# tvout_terminal_v1_1.net
KiCad netlist of a schematic drawn in EAGLE
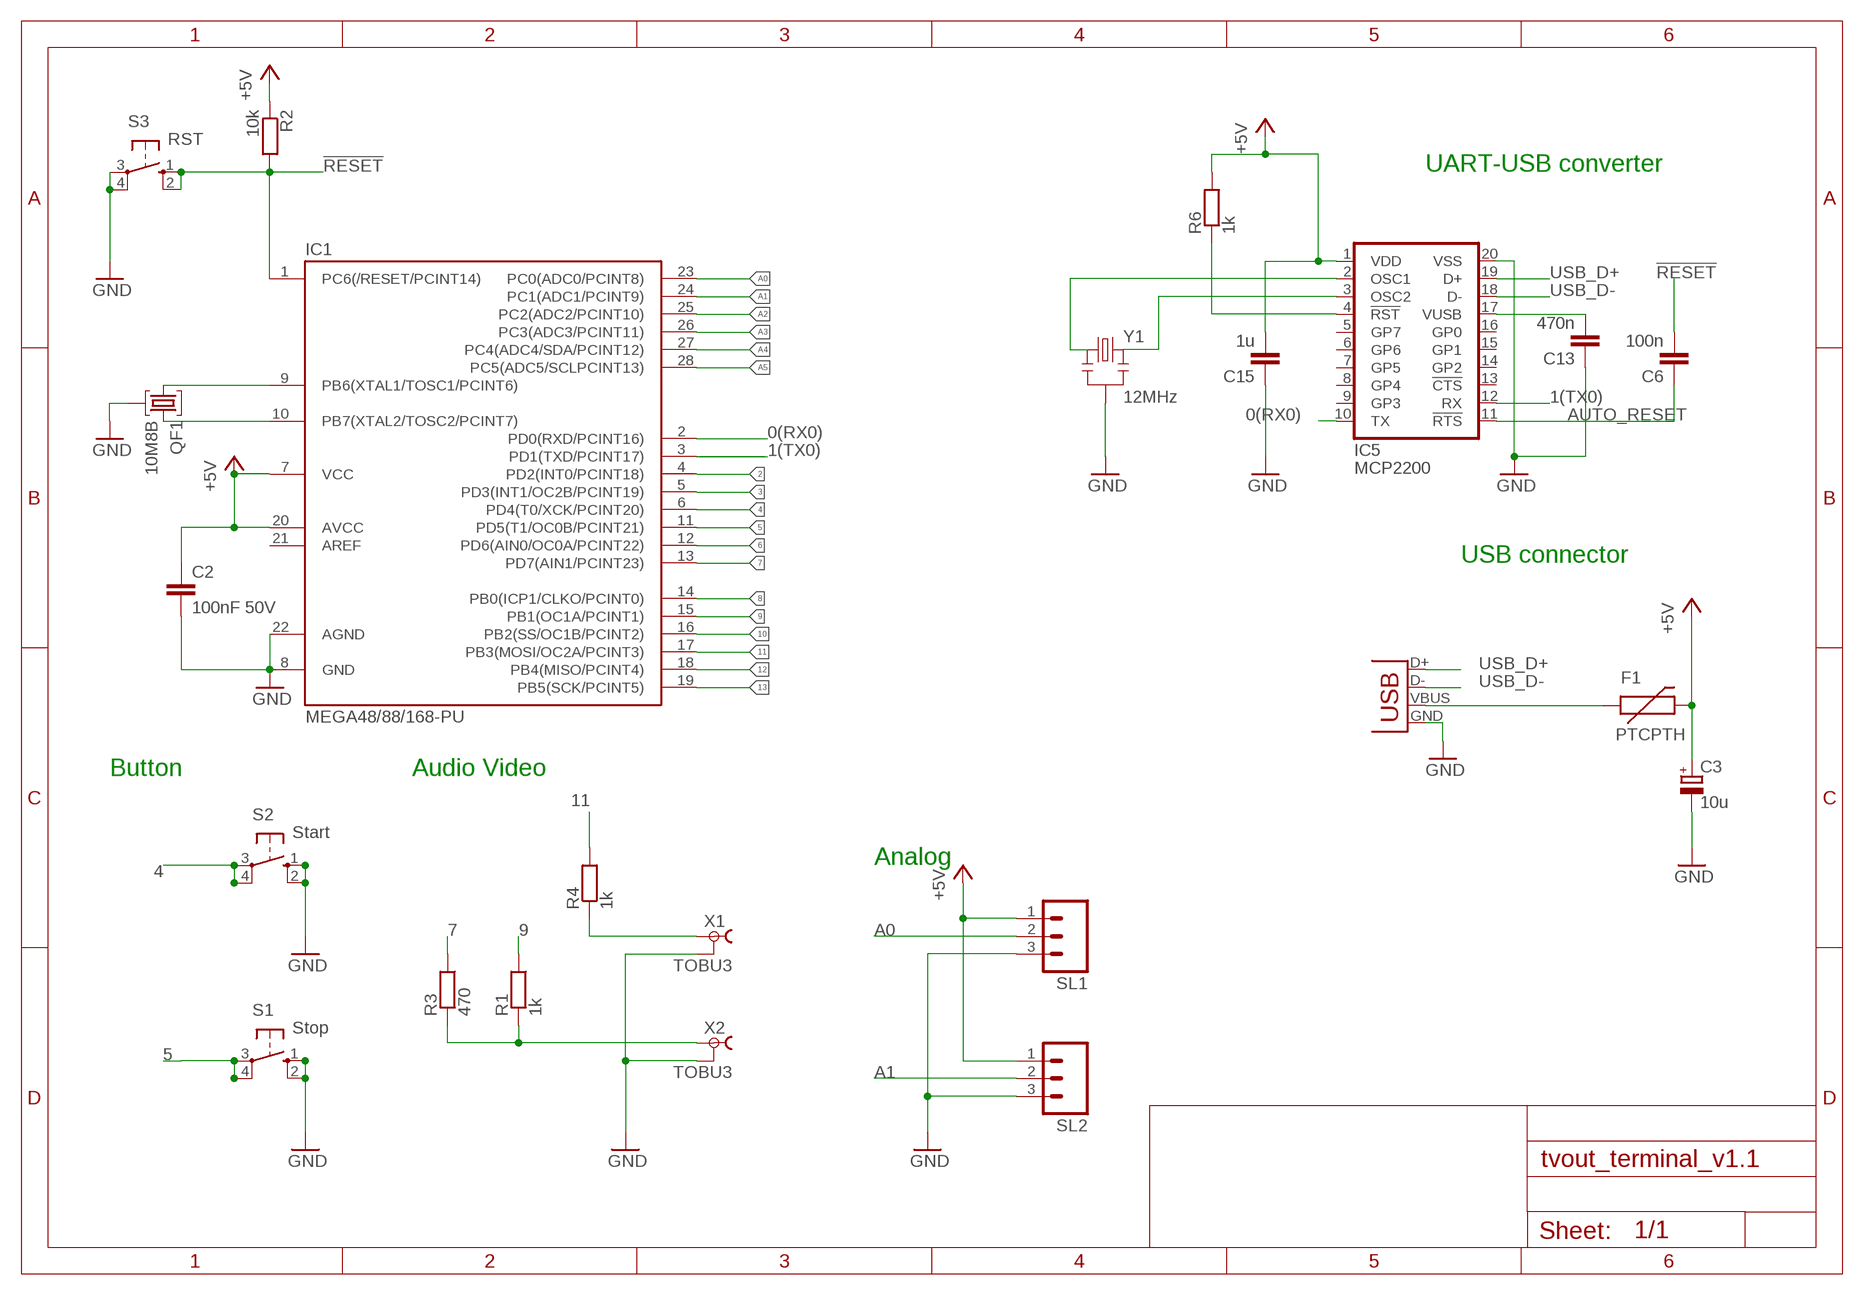
[diagram p0: schematic, sheet 1]

(export (version "E")
  (design (tool "Eeschema 10.0.6"))
  (components
    (comp (ref "C2")
      (value "100nF 50V")
      (footprint "eagle-import:C025-025X050")
      (libsource (lib "eagle-import") (part "C-EU025-025X050"))
    )
    (comp (ref "C3")
      (value "10u")
      (footprint "eagle-import:E2,5-7")
      (libsource (lib "eagle-import") (part "CPOL-EUE2.5-7"))
    )
    (comp (ref "C6")
      (value "100n")
      (footprint "eagle-import:CAP-PTH-SMALL")
      (libsource (lib "eagle-import") (part "CAPPTH"))
    )
    (comp (ref "C13")
      (value "470n")
      (footprint "eagle-import:CAP-PTH-SMALL")
      (libsource (lib "eagle-import") (part "CAPPTH"))
    )
    (comp (ref "C15")
      (value "1u")
      (footprint "eagle-import:CAP-PTH-5MM")
      (libsource (lib "eagle-import") (part "CAPPTH1"))
    )
    (comp (ref "F1")
      (value "PTCPTH")
      (footprint "eagle-import:PTC")
      (libsource (lib "eagle-import") (part "PTCPTH"))
    )
    (comp (ref "IC1")
      (value "MEGA48/88/168-PU")
      (footprint "eagle-import:DIL28-3")
      (libsource (lib "eagle-import") (part "MEGA48/88/168-PU"))
    )
    (comp (ref "IC5")
      (value "MCP2200")
      (footprint "eagle-import:SO20")
      (libsource (lib "eagle-import") (part "MCP2200"))
    )
    (comp (ref "QF1")
      (value "10M8B")
      (footprint "eagle-import:HC49U")
      (fields (field (name "OC_FARNELL") "1448129"))
      (libsource (lib "eagle-import") (part "10MB8"))
    )
    (comp (ref "R1")
      (value "1k")
      (footprint "eagle-import:RES-AXIAL-0.4")
      (libsource (lib "eagle-import") (part "RESISTOR"))
    )
    (comp (ref "R2")
      (value "10k")
      (footprint "eagle-import:RES-AXIAL-0.4")
      (libsource (lib "eagle-import") (part "RESISTOR"))
    )
    (comp (ref "R3")
      (value "470")
      (footprint "eagle-import:RES-AXIAL-0.4")
      (libsource (lib "eagle-import") (part "RESISTOR"))
    )
    (comp (ref "R4")
      (value "1k")
      (footprint "eagle-import:RES-AXIAL-0.4")
      (libsource (lib "eagle-import") (part "RESISTOR"))
    )
    (comp (ref "R6")
      (value "1k")
      (footprint "eagle-import:RES-AXIAL-0.4")
      (libsource (lib "eagle-import") (part "RESISTOR"))
    )
    (comp (ref "S1")
      (value "Stop")
      (footprint "eagle-import:B3F-10XX")
      (fields (field (name "MPN") "B3F-1000"))
      (libsource (lib "eagle-import") (part "10-XX"))
    )
    (comp (ref "S2")
      (value "Start")
      (footprint "eagle-import:B3F-10XX")
      (fields (field (name "MPN") "B3F-1000"))
      (libsource (lib "eagle-import") (part "10-XX"))
    )
    (comp (ref "S3")
      (value "RST")
      (footprint "eagle-import:B3F-10XX")
      (fields (field (name "MPN") "B3F-1000"))
      (libsource (lib "eagle-import") (part "10-XX"))
    )
    (comp (ref "SL1")
      (value "M03")
      (footprint "eagle-import:03P")
      (fields (field (name "OC_FARNELL") "1675765"))
      (libsource (lib "eagle-import") (part "M03"))
    )
    (comp (ref "SL2")
      (value "M03")
      (footprint "eagle-import:03P")
      (fields (field (name "OC_FARNELL") "1675765"))
      (libsource (lib "eagle-import") (part "M03"))
    )
    (comp (ref "X1")
      (value "TOBU3")
      (footprint "eagle-import:TOBU3")
      (fields (field (name "MF") "FARNELL") (field (name "MPN") "TOBU 3"))
      (libsource (lib "eagle-import") (part "TOBU3"))
    )
    (comp (ref "X2")
      (value "TOBU3")
      (footprint "eagle-import:TOBU3")
      (fields (field (name "MF") "FARNELL") (field (name "MPN") "TOBU 3"))
      (libsource (lib "eagle-import") (part "TOBU3"))
    )
    (comp (ref "X3")
      (value "USB")
      (footprint "eagle-import:USB-B-PTH")
      (libsource (lib "eagle-import") (part "USBPTH"))
    )
    (comp (ref "Y1")
      (value "12MHz")
      (footprint "eagle-import:HC49U-V-RESONATOR")
      (libsource (lib "eagle-import") (part "CRYSTAL-RESONATOR"))
    )
  )
  (nets
    (net (code "1") (name "+5V") (class "Default")
      (node (ref "C15") (pin "2") (pinfunction "2_2") (pintype "passive"))
      (node (ref "C2") (pin "1") (pinfunction "1_1") (pintype "passive"))
      (node (ref "C3") (pin "+") (pinfunction "+_+") (pintype "passive"))
      (node (ref "F1") (pin "P$2") (pinfunction "2_P$2") (pintype "bidirectional"))
      (node (ref "IC1") (pin "20") (pinfunction "AVCC_20") (pintype "passive"))
      (node (ref "IC1") (pin "7") (pinfunction "VCC_7") (pintype "power_in"))
      (node (ref "IC5") (pin "1") (pinfunction "VDD_1") (pintype "power_in"))
      (node (ref "R2") (pin "P$1") (pinfunction "1_P$1") (pintype "passive"))
      (node (ref "R6") (pin "P$2") (pinfunction "2_P$2") (pintype "passive"))
      (node (ref "SL1") (pin "1") (pinfunction "1_1") (pintype "passive"))
      (node (ref "SL2") (pin "1") (pinfunction "1_1") (pintype "passive"))
    )
    (net (code "2") (name "/0(RX0)") (class "Default")
      (node (ref "IC1") (pin "2") (pinfunction "PD0(RXD/PCINT16)_2") (pintype "bidirectional"))
      (node (ref "IC5") (pin "10") (pinfunction "TX_10") (pintype "bidirectional"))
    )
    (net (code "3") (name "/1(TX0)") (class "Default")
      (node (ref "IC1") (pin "3") (pinfunction "PD1(TXD/PCINT17)_3") (pintype "bidirectional"))
      (node (ref "IC5") (pin "12") (pinfunction "RX_12") (pintype "bidirectional"))
    )
    (net (code "4") (name "/AUTO_RESET") (class "Default")
      (node (ref "C6") (pin "1") (pinfunction "1_1") (pintype "passive"))
      (node (ref "IC5") (pin "11") (pinfunction "~{RTS}_11") (pintype "bidirectional"))
    )
    (net (code "5") (name "/USB_D+") (class "Default")
      (node (ref "IC5") (pin "19") (pinfunction "D+_19") (pintype "bidirectional"))
      (node (ref "X3") (pin "D+") (pinfunction "D+_D+") (pintype "bidirectional"))
    )
    (net (code "6") (name "/USB_D-") (class "Default")
      (node (ref "IC5") (pin "18") (pinfunction "D-_18") (pintype "bidirectional"))
      (node (ref "X3") (pin "D-") (pinfunction "D-_D-") (pintype "bidirectional"))
    )
    (net (code "7") (name "/~{RESET}") (class "Default")
      (node (ref "C6") (pin "2") (pinfunction "2_2") (pintype "passive"))
      (node (ref "IC1") (pin "1") (pinfunction "PC6(/RESET/PCINT14)_1") (pintype "bidirectional"))
      (node (ref "R2") (pin "P$2") (pinfunction "2_P$2") (pintype "passive"))
      (node (ref "S3") (pin "1") (pinfunction "S_1") (pintype "passive"))
      (node (ref "S3") (pin "2") (pinfunction "S1_2") (pintype "passive"))
    )
    (net (code "8") (name "2") (class "Default")
      (node (ref "IC1") (pin "4") (pinfunction "PD2(INT0/PCINT18)_4") (pintype "bidirectional"))
    )
    (net (code "9") (name "3") (class "Default")
      (node (ref "IC1") (pin "5") (pinfunction "PD3(INT1/OC2B/PCINT19)_5") (pintype "bidirectional"))
    )
    (net (code "10") (name "4") (class "Default")
      (node (ref "IC1") (pin "6") (pinfunction "PD4(T0/XCK/PCINT20)_6") (pintype "bidirectional"))
      (node (ref "S2") (pin "3") (pinfunction "P_3") (pintype "passive"))
      (node (ref "S2") (pin "4") (pinfunction "P1_4") (pintype "passive"))
    )
    (net (code "11") (name "5") (class "Default")
      (node (ref "IC1") (pin "11") (pinfunction "PD5(T1/OC0B/PCINT21)_11") (pintype "bidirectional"))
      (node (ref "S1") (pin "3") (pinfunction "P_3") (pintype "passive"))
      (node (ref "S1") (pin "4") (pinfunction "P1_4") (pintype "passive"))
    )
    (net (code "12") (name "6") (class "Default")
      (node (ref "IC1") (pin "12") (pinfunction "PD6(AIN0/OC0A/PCINT22)_12") (pintype "bidirectional"))
    )
    (net (code "13") (name "7") (class "Default")
      (node (ref "IC1") (pin "13") (pinfunction "PD7(AIN1/PCINT23)_13") (pintype "bidirectional"))
      (node (ref "R3") (pin "P$2") (pinfunction "2_P$2") (pintype "passive"))
    )
    (net (code "14") (name "8") (class "Default")
      (node (ref "IC1") (pin "14") (pinfunction "PB0(ICP1/CLKO/PCINT0)_14") (pintype "bidirectional"))
    )
    (net (code "15") (name "9") (class "Default")
      (node (ref "IC1") (pin "15") (pinfunction "PB1(OC1A/PCINT1)_15") (pintype "bidirectional"))
      (node (ref "R1") (pin "P$2") (pinfunction "2_P$2") (pintype "passive"))
    )
    (net (code "16") (name "10") (class "Default")
      (node (ref "IC1") (pin "16") (pinfunction "PB2(SS/OC1B/PCINT2)_16") (pintype "bidirectional"))
    )
    (net (code "17") (name "11") (class "Default")
      (node (ref "IC1") (pin "17") (pinfunction "PB3(MOSI/OC2A/PCINT3)_17") (pintype "bidirectional"))
      (node (ref "R4") (pin "P$2") (pinfunction "2_P$2") (pintype "passive"))
    )
    (net (code "18") (name "12") (class "Default")
      (node (ref "IC1") (pin "18") (pinfunction "PB4(MISO/PCINT4)_18") (pintype "bidirectional"))
    )
    (net (code "19") (name "13") (class "Default")
      (node (ref "IC1") (pin "19") (pinfunction "PB5(SCK/PCINT5)_19") (pintype "bidirectional"))
    )
    (net (code "20") (name "A0") (class "Default")
      (node (ref "IC1") (pin "23") (pinfunction "PC0(ADC0/PCINT8)_23") (pintype "bidirectional"))
      (node (ref "SL1") (pin "2") (pinfunction "2_2") (pintype "passive"))
    )
    (net (code "21") (name "A1") (class "Default")
      (node (ref "IC1") (pin "24") (pinfunction "PC1(ADC1/PCINT9)_24") (pintype "bidirectional"))
      (node (ref "SL2") (pin "2") (pinfunction "2_2") (pintype "passive"))
    )
    (net (code "22") (name "A2") (class "Default")
      (node (ref "IC1") (pin "25") (pinfunction "PC2(ADC2/PCINT10)_25") (pintype "bidirectional"))
    )
    (net (code "23") (name "A3") (class "Default")
      (node (ref "IC1") (pin "26") (pinfunction "PC3(ADC3/PCINT11)_26") (pintype "bidirectional"))
    )
    (net (code "24") (name "A4") (class "Default")
      (node (ref "IC1") (pin "27") (pinfunction "PC4(ADC4/SDA/PCINT12)_27") (pintype "bidirectional"))
    )
    (net (code "25") (name "A5") (class "Default")
      (node (ref "IC1") (pin "28") (pinfunction "PC5(ADC5/SCLPCINT13)_28") (pintype "bidirectional"))
    )
    (net (code "26") (name "GND") (class "Default")
      (node (ref "C13") (pin "1") (pinfunction "1_1") (pintype "passive"))
      (node (ref "C15") (pin "1") (pinfunction "1_1") (pintype "passive"))
      (node (ref "C2") (pin "2") (pinfunction "2_2") (pintype "passive"))
      (node (ref "C3") (pin "-") (pinfunction "-_-") (pintype "passive"))
      (node (ref "IC1") (pin "22") (pinfunction "AGND_22") (pintype "power_in"))
      (node (ref "IC1") (pin "8") (pinfunction "GND_8") (pintype "power_in"))
      (node (ref "IC5") (pin "20") (pinfunction "VSS_20") (pintype "power_in"))
      (node (ref "QF1") (pin "2") (pinfunction "2_2") (pintype "passive"))
      (node (ref "S1") (pin "1") (pinfunction "S_1") (pintype "passive"))
      (node (ref "S1") (pin "2") (pinfunction "S1_2") (pintype "passive"))
      (node (ref "S2") (pin "1") (pinfunction "S_1") (pintype "passive"))
      (node (ref "S2") (pin "2") (pinfunction "S1_2") (pintype "passive"))
      (node (ref "S3") (pin "3") (pinfunction "P_3") (pintype "passive"))
      (node (ref "S3") (pin "4") (pinfunction "P1_4") (pintype "passive"))
      (node (ref "SL1") (pin "3") (pinfunction "3_3") (pintype "passive"))
      (node (ref "SL2") (pin "3") (pinfunction "3_3") (pintype "passive"))
      (node (ref "X1") (pin "2") (pinfunction "2_2") (pintype "passive"))
      (node (ref "X1") (pin "2@1") (pinfunction "2_2@1") (pintype "passive"))
      (node (ref "X1") (pin "2@2") (pinfunction "2_2@2") (pintype "passive"))
      (node (ref "X2") (pin "2") (pinfunction "2_2") (pintype "passive"))
      (node (ref "X2") (pin "2@1") (pinfunction "2_2@1") (pintype "passive"))
      (node (ref "X2") (pin "2@2") (pinfunction "2_2@2") (pintype "passive"))
      (node (ref "X3") (pin "GND") (pinfunction "GND_GND") (pintype "bidirectional"))
      (node (ref "Y1") (pin "GND") (pinfunction "2_GND") (pintype "passive"))
    )
    (net (code "27") (name "Net-(F1-1)") (class "Default")
      (node (ref "F1") (pin "P$1") (pinfunction "1_P$1") (pintype "bidirectional"))
      (node (ref "X3") (pin "VBUS") (pinfunction "VBUS_VBUS") (pintype "bidirectional"))
    )
    (net (code "28") (name "Net-(IC1-PB6(XTAL1{slash}TOSC1{slash}PCINT6))") (class "Default")
      (node (ref "IC1") (pin "9") (pinfunction "PB6(XTAL1/TOSC1/PCINT6)_9") (pintype "bidirectional"))
      (node (ref "QF1") (pin "1") (pinfunction "1_1") (pintype "passive"))
    )
    (net (code "29") (name "Net-(IC1-PB7(XTAL2{slash}TOSC2{slash}PCINT7))") (class "Default")
      (node (ref "IC1") (pin "10") (pinfunction "PB7(XTAL2/TOSC2/PCINT7)_10") (pintype "bidirectional"))
      (node (ref "QF1") (pin "3") (pinfunction "3_3") (pintype "passive"))
    )
    (net (code "30") (name "Net-(IC5-OSC1)") (class "Default")
      (node (ref "IC5") (pin "2") (pinfunction "OSC1_2") (pintype "bidirectional"))
      (node (ref "Y1") (pin "1") (pinfunction "1_1") (pintype "passive"))
    )
    (net (code "31") (name "Net-(IC5-OSC2)") (class "Default")
      (node (ref "IC5") (pin "3") (pinfunction "OSC2_3") (pintype "bidirectional"))
      (node (ref "Y1") (pin "2") (pinfunction "3_2") (pintype "passive"))
    )
    (net (code "32") (name "Net-(IC5-VUSB)") (class "Default")
      (node (ref "C13") (pin "2") (pinfunction "2_2") (pintype "passive"))
      (node (ref "IC5") (pin "17") (pinfunction "VUSB_17") (pintype "bidirectional"))
    )
    (net (code "33") (name "Net-(IC5-~{RST})") (class "Default")
      (node (ref "IC5") (pin "4") (pinfunction "~{RST}_4") (pintype "bidirectional"))
      (node (ref "R6") (pin "P$1") (pinfunction "1_P$1") (pintype "passive"))
    )
    (net (code "34") (name "Net-(R1-1)") (class "Default")
      (node (ref "R1") (pin "P$1") (pinfunction "1_P$1") (pintype "passive"))
      (node (ref "R3") (pin "P$1") (pinfunction "1_P$1") (pintype "passive"))
      (node (ref "X2") (pin "1") (pinfunction "1_1") (pintype "passive"))
    )
    (net (code "35") (name "Net-(R4-1)") (class "Default")
      (node (ref "R4") (pin "P$1") (pinfunction "1_P$1") (pintype "passive"))
      (node (ref "X1") (pin "1") (pinfunction "1_1") (pintype "passive"))
    )
    (net (code "36") (name "unconnected-(IC1-AREF-Pad21)") (class "Default")
      (node (ref "IC1") (pin "21") (pinfunction "AREF_21") (pintype "passive"))
    )
    (net (code "37") (name "unconnected-(IC5-GP0-Pad16)") (class "Default")
      (node (ref "IC5") (pin "16") (pinfunction "GP0_16") (pintype "bidirectional"))
    )
    (net (code "38") (name "unconnected-(IC5-GP1-Pad15)") (class "Default")
      (node (ref "IC5") (pin "15") (pinfunction "GP1_15") (pintype "bidirectional"))
    )
    (net (code "39") (name "unconnected-(IC5-GP2-Pad14)") (class "Default")
      (node (ref "IC5") (pin "14") (pinfunction "GP2_14") (pintype "bidirectional"))
    )
    (net (code "40") (name "unconnected-(IC5-GP3-Pad9)") (class "Default")
      (node (ref "IC5") (pin "9") (pinfunction "GP3_9") (pintype "bidirectional"))
    )
    (net (code "41") (name "unconnected-(IC5-GP4-Pad8)") (class "Default")
      (node (ref "IC5") (pin "8") (pinfunction "GP4_8") (pintype "bidirectional"))
    )
    (net (code "42") (name "unconnected-(IC5-GP5-Pad7)") (class "Default")
      (node (ref "IC5") (pin "7") (pinfunction "GP5_7") (pintype "bidirectional"))
    )
    (net (code "43") (name "unconnected-(IC5-GP6-Pad6)") (class "Default")
      (node (ref "IC5") (pin "6") (pinfunction "GP6_6") (pintype "bidirectional"))
    )
    (net (code "44") (name "unconnected-(IC5-GP7-Pad5)") (class "Default")
      (node (ref "IC5") (pin "5") (pinfunction "GP7_5") (pintype "bidirectional"))
    )
    (net (code "45") (name "unconnected-(IC5-~{CTS}-Pad13)") (class "Default")
      (node (ref "IC5") (pin "13") (pinfunction "~{CTS}_13") (pintype "bidirectional"))
    )
  )
)
